# Uh-Oh_Battery_Indicator.net
KiCad netlist of a schematic drawn in EAGLE
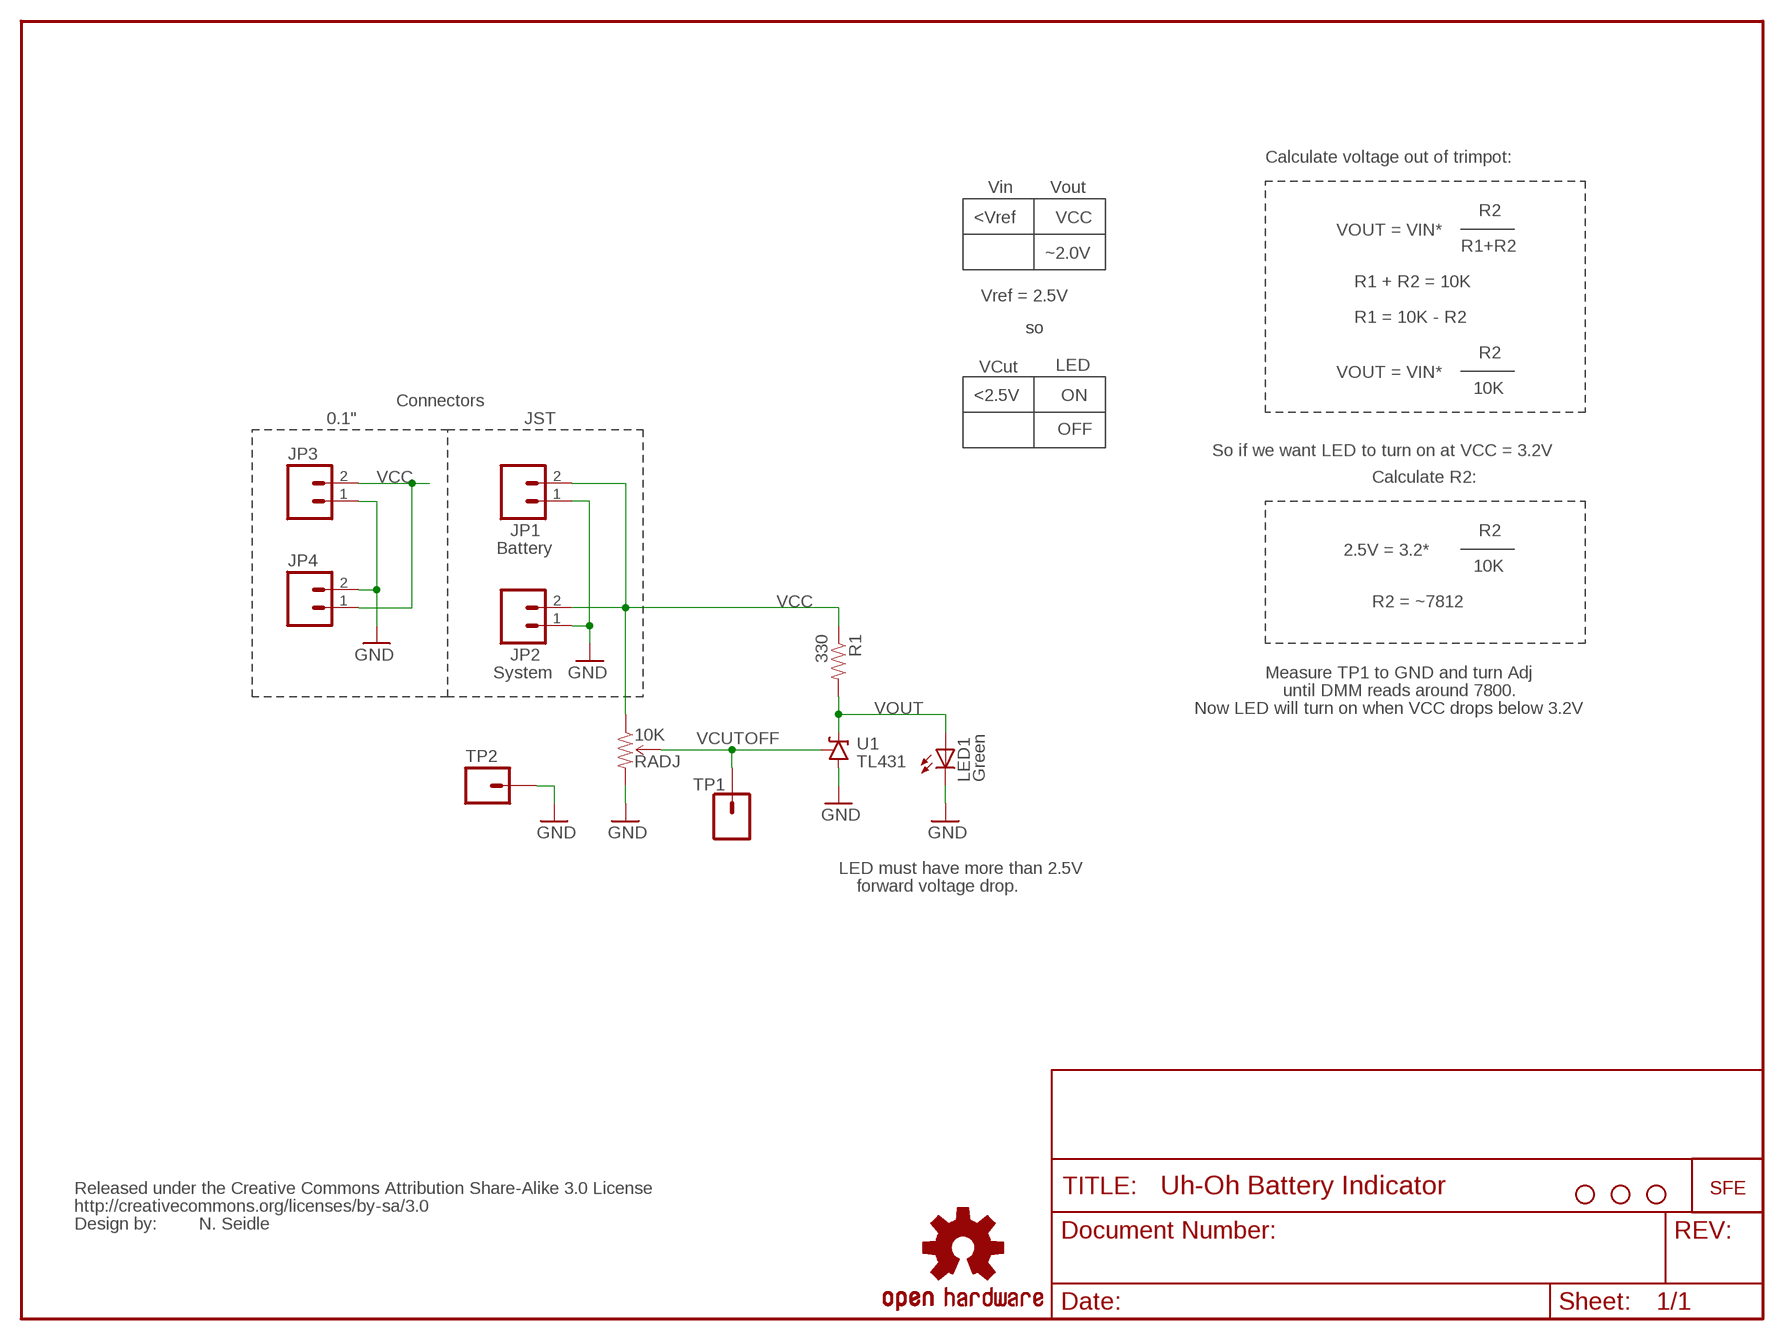
[diagram p0: schematic, sheet 1]

(export (version "E")
  (design (tool "Eeschema 10.0.6"))
  (components
    (comp (ref "JP1")
      (value "Battery")
      (footprint "eagle-import:JST-2-PTH")
      (libsource (lib "eagle-import") (part "M02JST-PTH-2"))
    )
    (comp (ref "JP2")
      (value "System")
      (footprint "eagle-import:JST-2-PTH")
      (libsource (lib "eagle-import") (part "M02JST-PTH-2"))
    )
    (comp (ref "JP3")
      (value "M02PTH")
      (footprint "eagle-import:1X02")
      (libsource (lib "eagle-import") (part "M02PTH"))
    )
    (comp (ref "JP4")
      (value "M02PTH")
      (footprint "eagle-import:1X02")
      (libsource (lib "eagle-import") (part "M02PTH"))
    )
    (comp (ref "JP31")
      (value "STAND-OFF")
      (footprint "eagle-import:STAND-OFF")
      (libsource (lib "eagle-import") (part "STAND-OFF"))
    )
    (comp (ref "JP41")
      (value "STAND-OFF")
      (footprint "eagle-import:STAND-OFF")
      (libsource (lib "eagle-import") (part "STAND-OFF"))
    )
    (comp (ref "JP51")
      (value "LOGO-SFENEW")
      (footprint "eagle-import:SFE-NEW-WEBLOGO")
      (libsource (lib "eagle-import") (part "LOGO-SFENEW"))
    )
    (comp (ref "JP61")
      (value "STAND-OFF")
      (footprint "eagle-import:STAND-OFF")
      (libsource (lib "eagle-import") (part "STAND-OFF"))
    )
    (comp (ref "LED1")
      (value "Green")
      (footprint "eagle-import:LED10MM-2")
      (libsource (lib "eagle-import") (part "LED10MM2"))
    )
    (comp (ref "R1")
      (value "330")
      (footprint "eagle-import:AXIAL-0.3")
      (libsource (lib "eagle-import") (part "RESISTORAXIAL-0.3"))
    )
    (comp (ref "RADJ")
      (value "10K")
      (footprint "eagle-import:3386U")
      (libsource (lib "eagle-import") (part "TRIMPOT-PTH-KNOB"))
    )
    (comp (ref "TP1")
      (value "TP1")
      (footprint "eagle-import:1X01")
      (libsource (lib "eagle-import") (part "M01PTH"))
    )
    (comp (ref "TP2")
      (value "TP2")
      (footprint "eagle-import:1X01")
      (libsource (lib "eagle-import") (part "M01PTH"))
    )
    (comp (ref "U$1")
      (value "OSHW-LOGOS")
      (footprint "eagle-import:OSHW-LOGO-S")
      (libsource (lib "eagle-import") (part "OSHW-LOGOS"))
    )
    (comp (ref "U$2")
      (value "CREATIVE_COMMONS")
      (footprint "eagle-import:CREATIVE_COMMONS")
      (libsource (lib "eagle-import") (part "CREATIVE_COMMONS"))
    )
    (comp (ref "U1")
      (value "TL431")
      (footprint "eagle-import:TO-92")
      (libsource (lib "eagle-import") (part "TL431PTH"))
    )
  )
  (nets
    (net (code "1") (name "/VCC") (class "Default")
      (node (ref "JP1") (pin "2") (pinfunction "2_2") (pintype "passive"))
      (node (ref "JP2") (pin "2") (pinfunction "2_2") (pintype "passive"))
      (node (ref "JP3") (pin "2") (pinfunction "2_2") (pintype "passive"))
      (node (ref "JP4") (pin "1") (pinfunction "1_1") (pintype "passive"))
      (node (ref "R1") (pin "P$1") (pinfunction "1_P$1") (pintype "passive"))
      (node (ref "RADJ") (pin "1") (pinfunction "CCW_1") (pintype "passive"))
    )
    (net (code "2") (name "/VCUTOFF") (class "Default")
      (node (ref "RADJ") (pin "2") (pinfunction "WIPER_2") (pintype "passive"))
      (node (ref "TP1") (pin "1") (pinfunction "1_1") (pintype "passive"))
      (node (ref "U1") (pin "1") (pinfunction "R_1") (pintype "bidirectional"))
    )
    (net (code "3") (name "/VOUT") (class "Default")
      (node (ref "LED1") (pin "A") (pinfunction "A_A") (pintype "passive"))
      (node (ref "R1") (pin "P$2") (pinfunction "2_P$2") (pintype "passive"))
      (node (ref "U1") (pin "3") (pinfunction "C_3") (pintype "passive"))
    )
    (net (code "4") (name "GND") (class "Default")
      (node (ref "JP1") (pin "1") (pinfunction "1_1") (pintype "passive"))
      (node (ref "JP2") (pin "1") (pinfunction "1_1") (pintype "passive"))
      (node (ref "JP3") (pin "1") (pinfunction "1_1") (pintype "passive"))
      (node (ref "JP4") (pin "2") (pinfunction "2_2") (pintype "passive"))
      (node (ref "LED1") (pin "K") (pinfunction "C_K") (pintype "passive"))
      (node (ref "RADJ") (pin "3") (pinfunction "CW_3") (pintype "passive"))
      (node (ref "TP2") (pin "1") (pinfunction "1_1") (pintype "passive"))
      (node (ref "U1") (pin "2") (pinfunction "A_2") (pintype "passive"))
    )
  )
)
